# LED.net
KiCad netlist of a schematic drawn in EAGLE
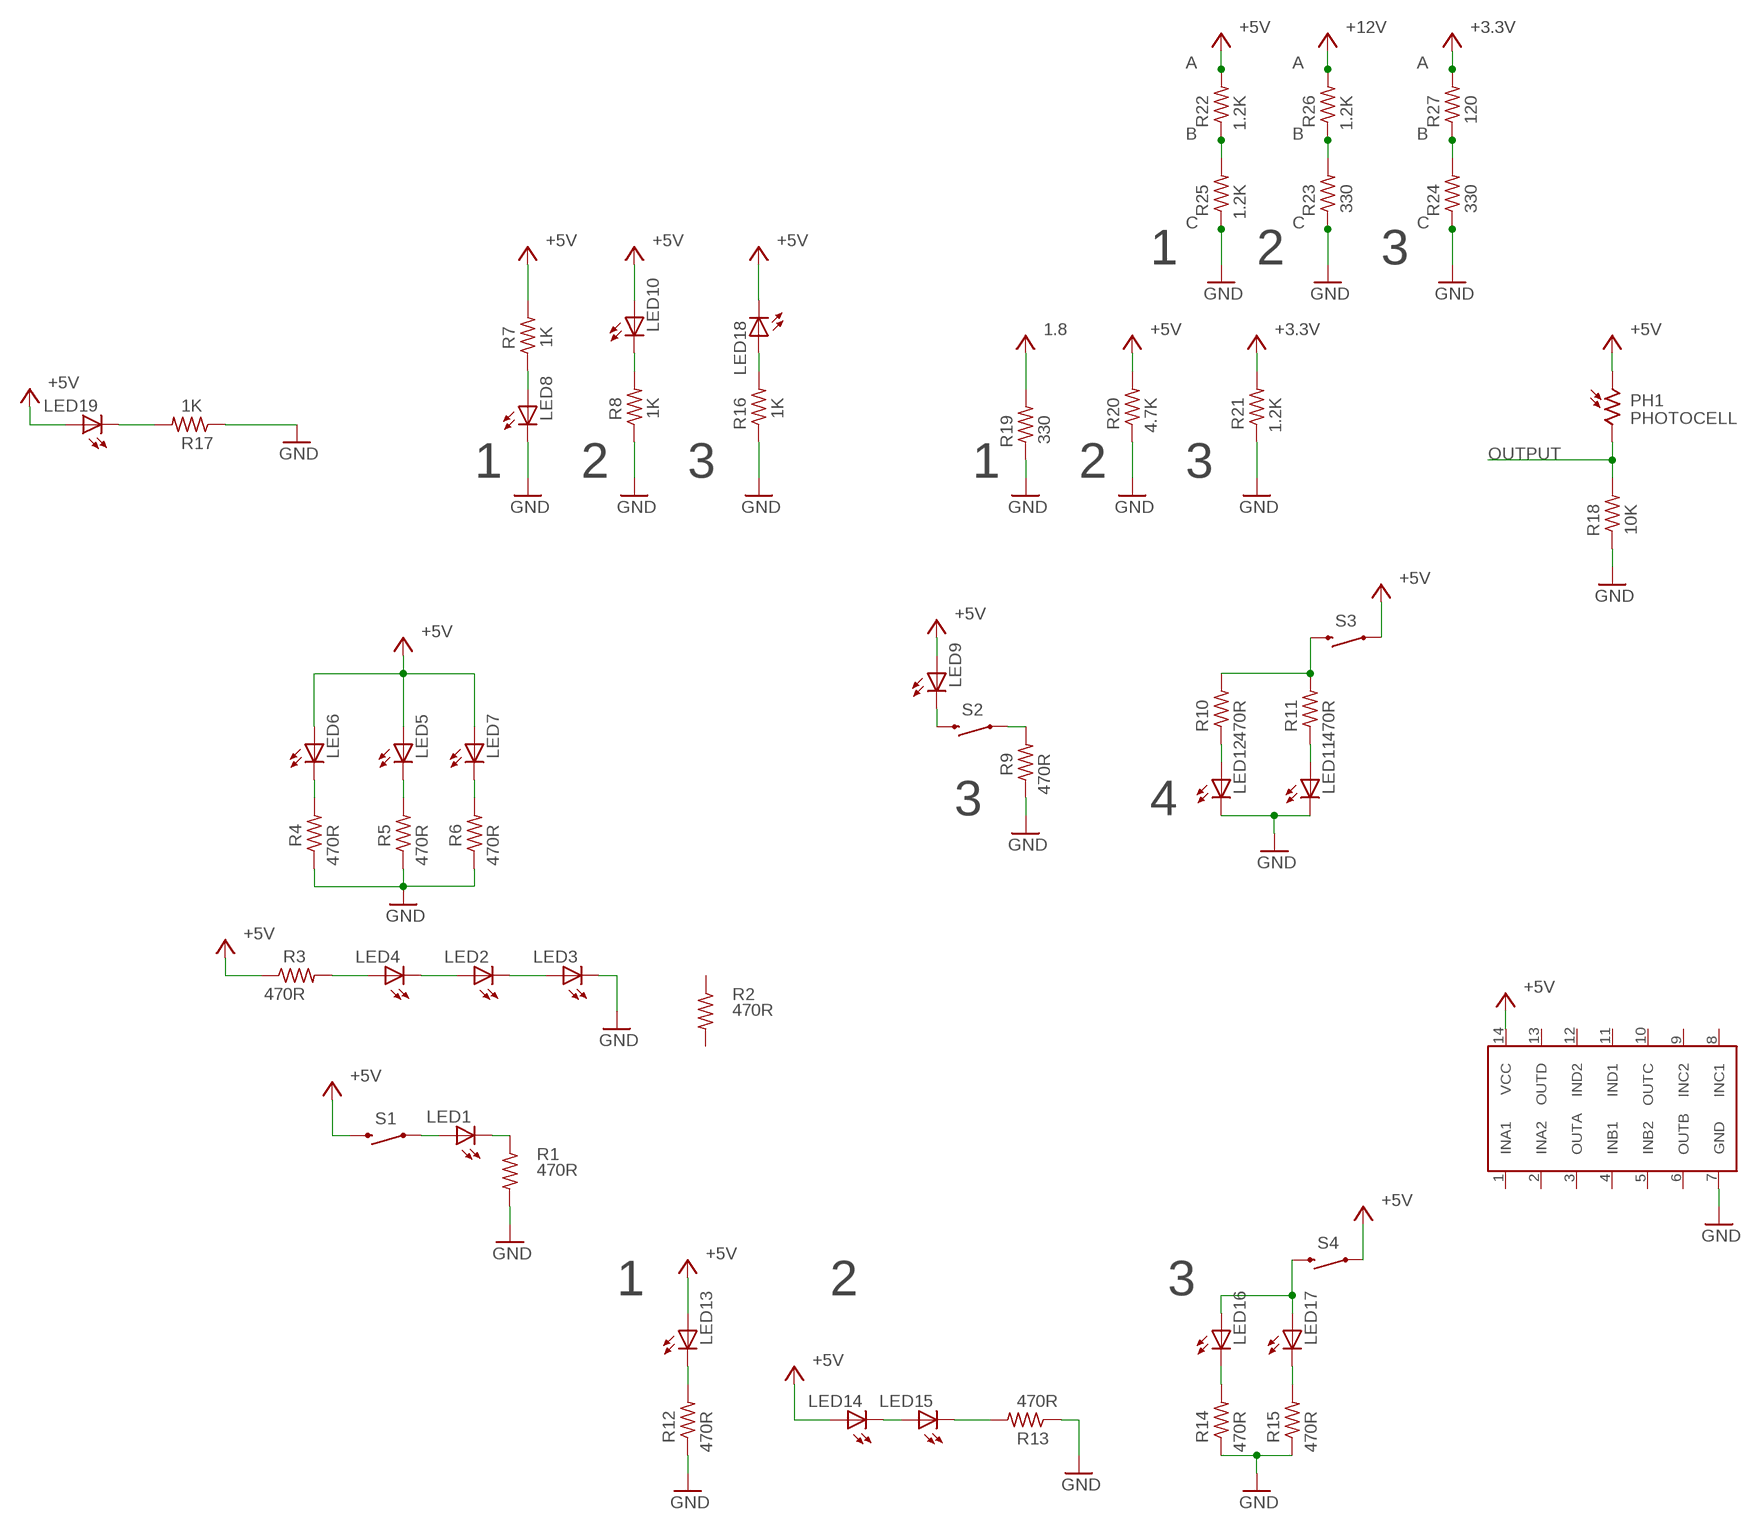
[diagram p0: schematic, sheet 1]

(export (version "E")
  (design (tool "Eeschema 10.0.6"))
  (components
    (comp (ref "LED1")
      (value "LAP4-BOTTOM")
      (footprint "eagle-import:P47F-BOTTOM")
      (libsource (lib "eagle-import") (part "P4-BOTTOMLA"))
    )
    (comp (ref "LED2")
      (value "LAP4-BOTTOM")
      (footprint "eagle-import:P47F-BOTTOM")
      (libsource (lib "eagle-import") (part "P4-BOTTOMLA"))
    )
    (comp (ref "LED3")
      (value "LAP4-BOTTOM")
      (footprint "eagle-import:P47F-BOTTOM")
      (libsource (lib "eagle-import") (part "P4-BOTTOMLA"))
    )
    (comp (ref "LED4")
      (value "LAP4-BOTTOM")
      (footprint "eagle-import:P47F-BOTTOM")
      (libsource (lib "eagle-import") (part "P4-BOTTOMLA"))
    )
    (comp (ref "LED5")
      (value "LAP4-BOTTOM")
      (footprint "eagle-import:P47F-BOTTOM")
      (libsource (lib "eagle-import") (part "P4-BOTTOMLA"))
    )
    (comp (ref "LED6")
      (value "LAP4-BOTTOM")
      (footprint "eagle-import:P47F-BOTTOM")
      (libsource (lib "eagle-import") (part "P4-BOTTOMLA"))
    )
    (comp (ref "LED7")
      (value "LAP4-BOTTOM")
      (footprint "eagle-import:P47F-BOTTOM")
      (libsource (lib "eagle-import") (part "P4-BOTTOMLA"))
    )
    (comp (ref "LED8")
      (value "LAP4-BOTTOM")
      (footprint "eagle-import:P47F-BOTTOM")
      (libsource (lib "eagle-import") (part "P4-BOTTOMLA"))
    )
    (comp (ref "LED9")
      (value "LAP4-BOTTOM")
      (footprint "eagle-import:P47F-BOTTOM")
      (libsource (lib "eagle-import") (part "P4-BOTTOMLA"))
    )
    (comp (ref "LED10")
      (value "LAP4-BOTTOM")
      (footprint "eagle-import:P47F-BOTTOM")
      (libsource (lib "eagle-import") (part "P4-BOTTOMLA"))
    )
    (comp (ref "LED11")
      (value "LAP4-BOTTOM")
      (footprint "eagle-import:P47F-BOTTOM")
      (libsource (lib "eagle-import") (part "P4-BOTTOMLA"))
    )
    (comp (ref "LED12")
      (value "LAP4-BOTTOM")
      (footprint "eagle-import:P47F-BOTTOM")
      (libsource (lib "eagle-import") (part "P4-BOTTOMLA"))
    )
    (comp (ref "LED13")
      (value "LAP4-BOTTOM")
      (footprint "eagle-import:P47F-BOTTOM")
      (libsource (lib "eagle-import") (part "P4-BOTTOMLA"))
    )
    (comp (ref "LED14")
      (value "LAP4-BOTTOM")
      (footprint "eagle-import:P47F-BOTTOM")
      (libsource (lib "eagle-import") (part "P4-BOTTOMLA"))
    )
    (comp (ref "LED15")
      (value "LAP4-BOTTOM")
      (footprint "eagle-import:P47F-BOTTOM")
      (libsource (lib "eagle-import") (part "P4-BOTTOMLA"))
    )
    (comp (ref "LED16")
      (value "LAP4-BOTTOM")
      (footprint "eagle-import:P47F-BOTTOM")
      (libsource (lib "eagle-import") (part "P4-BOTTOMLA"))
    )
    (comp (ref "LED17")
      (value "LAP4-BOTTOM")
      (footprint "eagle-import:P47F-BOTTOM")
      (libsource (lib "eagle-import") (part "P4-BOTTOMLA"))
    )
    (comp (ref "LED18")
      (value "LAP4-BOTTOM")
      (footprint "eagle-import:P47F-BOTTOM")
      (libsource (lib "eagle-import") (part "P4-BOTTOMLA"))
    )
    (comp (ref "LED19")
      (value "LAP4-BOTTOM")
      (footprint "eagle-import:P47F-BOTTOM")
      (libsource (lib "eagle-import") (part "P4-BOTTOMLA"))
    )
    (comp (ref "PH1")
      (value "PHOTOCELL")
      (footprint "eagle-import:D11XX_H")
      (libsource (lib "eagle-import") (part "PHOTOCELLD11"))
    )
    (comp (ref "R1")
      (value "470R")
      (footprint "eagle-import:0207_12")
      (libsource (lib "eagle-import") (part "R-US_0207/12"))
    )
    (comp (ref "R2")
      (value "470R")
      (footprint "eagle-import:0207_12")
      (libsource (lib "eagle-import") (part "R-US_0207/12"))
    )
    (comp (ref "R3")
      (value "470R")
      (footprint "eagle-import:0207_12")
      (libsource (lib "eagle-import") (part "R-US_0207/12"))
    )
    (comp (ref "R4")
      (value "470R")
      (footprint "eagle-import:0207_12")
      (libsource (lib "eagle-import") (part "R-US_0207/12"))
    )
    (comp (ref "R5")
      (value "470R")
      (footprint "eagle-import:0207_12")
      (libsource (lib "eagle-import") (part "R-US_0207/12"))
    )
    (comp (ref "R6")
      (value "470R")
      (footprint "eagle-import:0207_12")
      (libsource (lib "eagle-import") (part "R-US_0207/12"))
    )
    (comp (ref "R7")
      (value "1K")
      (footprint "eagle-import:0207_12")
      (libsource (lib "eagle-import") (part "R-US_0207/12"))
    )
    (comp (ref "R8")
      (value "1K")
      (footprint "eagle-import:0207_12")
      (libsource (lib "eagle-import") (part "R-US_0207/12"))
    )
    (comp (ref "R9")
      (value "470R")
      (footprint "eagle-import:0207_12")
      (libsource (lib "eagle-import") (part "R-US_0207/12"))
    )
    (comp (ref "R10")
      (value "470R")
      (footprint "eagle-import:0207_12")
      (libsource (lib "eagle-import") (part "R-US_0207/12"))
    )
    (comp (ref "R11")
      (value "470R")
      (footprint "eagle-import:0207_12")
      (libsource (lib "eagle-import") (part "R-US_0207/12"))
    )
    (comp (ref "R12")
      (value "470R")
      (footprint "eagle-import:0207_12")
      (libsource (lib "eagle-import") (part "R-US_0207/12"))
    )
    (comp (ref "R13")
      (value "470R")
      (footprint "eagle-import:0207_12")
      (libsource (lib "eagle-import") (part "R-US_0207/12"))
    )
    (comp (ref "R14")
      (value "470R")
      (footprint "eagle-import:0207_12")
      (libsource (lib "eagle-import") (part "R-US_0207/12"))
    )
    (comp (ref "R15")
      (value "470R")
      (footprint "eagle-import:0207_12")
      (libsource (lib "eagle-import") (part "R-US_0207/12"))
    )
    (comp (ref "R16")
      (value "1K")
      (footprint "eagle-import:0207_12")
      (libsource (lib "eagle-import") (part "R-US_0207/12"))
    )
    (comp (ref "R17")
      (value "1K")
      (footprint "eagle-import:0207_12")
      (libsource (lib "eagle-import") (part "R-US_0207/12"))
    )
    (comp (ref "R18")
      (value "10K")
      (footprint "eagle-import:0207_12")
      (libsource (lib "eagle-import") (part "R-US_0207/12"))
    )
    (comp (ref "R19")
      (value "330")
      (footprint "eagle-import:0207_12")
      (libsource (lib "eagle-import") (part "R-US_0207/12"))
    )
    (comp (ref "R20")
      (value "4.7K")
      (footprint "eagle-import:0207_12")
      (libsource (lib "eagle-import") (part "R-US_0207/12"))
    )
    (comp (ref "R21")
      (value "1.2K")
      (footprint "eagle-import:0207_12")
      (libsource (lib "eagle-import") (part "R-US_0207/12"))
    )
    (comp (ref "R22")
      (value "1.2K")
      (footprint "eagle-import:0207_12")
      (libsource (lib "eagle-import") (part "R-US_0207/12"))
    )
    (comp (ref "R23")
      (value "330")
      (footprint "eagle-import:0207_12")
      (libsource (lib "eagle-import") (part "R-US_0207/12"))
    )
    (comp (ref "R24")
      (value "330")
      (footprint "eagle-import:0207_12")
      (libsource (lib "eagle-import") (part "R-US_0207/12"))
    )
    (comp (ref "R25")
      (value "1.2K")
      (footprint "eagle-import:0207_12")
      (libsource (lib "eagle-import") (part "R-US_0207/12"))
    )
    (comp (ref "R26")
      (value "1.2K")
      (footprint "eagle-import:0207_12")
      (libsource (lib "eagle-import") (part "R-US_0207/12"))
    )
    (comp (ref "R27")
      (value "120")
      (footprint "eagle-import:0207_12")
      (libsource (lib "eagle-import") (part "R-US_0207/12"))
    )
    (comp (ref "S1")
      (value "MOMENTARY-SWITCH-SPST-PTH-6.0MM")
      (footprint "eagle-import:TACTILE_SWITCH_PTH_6.0MM")
      (libsource (lib "eagle-import") (part "MOMENTARY-SWITCH-SPST-PTH-6.0MM"))
    )
    (comp (ref "S2")
      (value "MOMENTARY-SWITCH-SPST-PTH-6.0MM")
      (footprint "eagle-import:TACTILE_SWITCH_PTH_6.0MM")
      (libsource (lib "eagle-import") (part "MOMENTARY-SWITCH-SPST-PTH-6.0MM"))
    )
    (comp (ref "S3")
      (value "MOMENTARY-SWITCH-SPST-PTH-6.0MM")
      (footprint "eagle-import:TACTILE_SWITCH_PTH_6.0MM")
      (libsource (lib "eagle-import") (part "MOMENTARY-SWITCH-SPST-PTH-6.0MM"))
    )
    (comp (ref "S4")
      (value "MOMENTARY-SWITCH-SPST-PTH-6.0MM")
      (footprint "eagle-import:TACTILE_SWITCH_PTH_6.0MM")
      (libsource (lib "eagle-import") (part "MOMENTARY-SWITCH-SPST-PTH-6.0MM"))
    )
    (comp (ref "U$1")
      (value "7408")
      (footprint "eagle-import:DIL14")
      (libsource (lib "eagle-import") (part "7408"))
    )
  )
  (nets
    (net (code "1") (name "+12V") (class "Default")
      (node (ref "LED10") (pin "A") (pinfunction "A_A") (pintype "passive"))
      (node (ref "LED13") (pin "A") (pinfunction "A_A") (pintype "passive"))
      (node (ref "LED14") (pin "A") (pinfunction "A_A") (pintype "passive"))
      (node (ref "LED18") (pin "C") (pinfunction "C_C") (pintype "passive"))
      (node (ref "LED19") (pin "A") (pinfunction "A_A") (pintype "passive"))
      (node (ref "LED5") (pin "A") (pinfunction "A_A") (pintype "passive"))
      (node (ref "LED6") (pin "A") (pinfunction "A_A") (pintype "passive"))
      (node (ref "LED7") (pin "A") (pinfunction "A_A") (pintype "passive"))
      (node (ref "LED9") (pin "A") (pinfunction "A_A") (pintype "passive"))
      (node (ref "PH1") (pin "1") (pinfunction "1_1") (pintype "passive"))
      (node (ref "R19") (pin "2") (pinfunction "2_2") (pintype "passive"))
      (node (ref "R20") (pin "2") (pinfunction "2_2") (pintype "passive"))
      (node (ref "R21") (pin "2") (pinfunction "2_2") (pintype "passive"))
      (node (ref "R22") (pin "2") (pinfunction "2_2") (pintype "passive"))
      (node (ref "R26") (pin "2") (pinfunction "2_2") (pintype "passive"))
      (node (ref "R27") (pin "2") (pinfunction "2_2") (pintype "passive"))
      (node (ref "R3") (pin "1") (pinfunction "1_1") (pintype "passive"))
      (node (ref "R7") (pin "2") (pinfunction "2_2") (pintype "passive"))
      (node (ref "S1") (pin "3") (pinfunction "2_3") (pintype "passive"))
      (node (ref "S3") (pin "1") (pinfunction "1_1") (pintype "passive"))
      (node (ref "S4") (pin "1") (pinfunction "1_1") (pintype "passive"))
      (node (ref "U$1") (pin "14") (pinfunction "VCC_14") (pintype "bidirectional"))
    )
    (net (code "2") (name "GND") (class "Default")
      (node (ref "LED11") (pin "C") (pinfunction "C_C") (pintype "passive"))
      (node (ref "LED12") (pin "C") (pinfunction "C_C") (pintype "passive"))
      (node (ref "LED3") (pin "C") (pinfunction "C_C") (pintype "passive"))
      (node (ref "LED8") (pin "C") (pinfunction "C_C") (pintype "passive"))
      (node (ref "R1") (pin "2") (pinfunction "2_2") (pintype "passive"))
      (node (ref "R12") (pin "1") (pinfunction "1_1") (pintype "passive"))
      (node (ref "R13") (pin "1") (pinfunction "1_1") (pintype "passive"))
      (node (ref "R14") (pin "1") (pinfunction "1_1") (pintype "passive"))
      (node (ref "R15") (pin "1") (pinfunction "1_1") (pintype "passive"))
      (node (ref "R16") (pin "1") (pinfunction "1_1") (pintype "passive"))
      (node (ref "R17") (pin "1") (pinfunction "1_1") (pintype "passive"))
      (node (ref "R18") (pin "1") (pinfunction "1_1") (pintype "passive"))
      (node (ref "R19") (pin "1") (pinfunction "1_1") (pintype "passive"))
      (node (ref "R20") (pin "1") (pinfunction "1_1") (pintype "passive"))
      (node (ref "R21") (pin "1") (pinfunction "1_1") (pintype "passive"))
      (node (ref "R23") (pin "1") (pinfunction "1_1") (pintype "passive"))
      (node (ref "R24") (pin "1") (pinfunction "1_1") (pintype "passive"))
      (node (ref "R25") (pin "1") (pinfunction "1_1") (pintype "passive"))
      (node (ref "R4") (pin "1") (pinfunction "1_1") (pintype "passive"))
      (node (ref "R5") (pin "1") (pinfunction "1_1") (pintype "passive"))
      (node (ref "R6") (pin "1") (pinfunction "1_1") (pintype "passive"))
      (node (ref "R8") (pin "1") (pinfunction "1_1") (pintype "passive"))
      (node (ref "R9") (pin "1") (pinfunction "1_1") (pintype "passive"))
      (node (ref "U$1") (pin "7") (pinfunction "GND_7") (pintype "bidirectional"))
    )
    (net (code "3") (name "Net-(LED1-PadA)") (class "Default")
      (node (ref "LED1") (pin "A") (pinfunction "A_A") (pintype "passive"))
      (node (ref "S1") (pin "1") (pinfunction "1_1") (pintype "passive"))
    )
    (net (code "4") (name "Net-(LED1-PadC)") (class "Default")
      (node (ref "LED1") (pin "C") (pinfunction "C_C") (pintype "passive"))
      (node (ref "R1") (pin "1") (pinfunction "1_1") (pintype "passive"))
    )
    (net (code "5") (name "Net-(LED2-PadA)") (class "Default")
      (node (ref "LED2") (pin "A") (pinfunction "A_A") (pintype "passive"))
      (node (ref "LED4") (pin "C") (pinfunction "C_C") (pintype "passive"))
    )
    (net (code "6") (name "Net-(LED2-PadC)") (class "Default")
      (node (ref "LED2") (pin "C") (pinfunction "C_C") (pintype "passive"))
      (node (ref "LED3") (pin "A") (pinfunction "A_A") (pintype "passive"))
    )
    (net (code "7") (name "Net-(LED4-PadA)") (class "Default")
      (node (ref "LED4") (pin "A") (pinfunction "A_A") (pintype "passive"))
      (node (ref "R3") (pin "2") (pinfunction "2_2") (pintype "passive"))
    )
    (net (code "8") (name "Net-(LED5-PadC)") (class "Default")
      (node (ref "LED5") (pin "C") (pinfunction "C_C") (pintype "passive"))
      (node (ref "R5") (pin "2") (pinfunction "2_2") (pintype "passive"))
    )
    (net (code "9") (name "Net-(LED6-PadC)") (class "Default")
      (node (ref "LED6") (pin "C") (pinfunction "C_C") (pintype "passive"))
      (node (ref "R4") (pin "2") (pinfunction "2_2") (pintype "passive"))
    )
    (net (code "10") (name "Net-(LED7-PadC)") (class "Default")
      (node (ref "LED7") (pin "C") (pinfunction "C_C") (pintype "passive"))
      (node (ref "R6") (pin "2") (pinfunction "2_2") (pintype "passive"))
    )
    (net (code "11") (name "Net-(LED8-PadA)") (class "Default")
      (node (ref "LED8") (pin "A") (pinfunction "A_A") (pintype "passive"))
      (node (ref "R7") (pin "1") (pinfunction "1_1") (pintype "passive"))
    )
    (net (code "12") (name "Net-(LED10-PadC)") (class "Default")
      (node (ref "LED10") (pin "C") (pinfunction "C_C") (pintype "passive"))
      (node (ref "R8") (pin "2") (pinfunction "2_2") (pintype "passive"))
    )
    (net (code "13") (name "Net-(LED11-PadA)") (class "Default")
      (node (ref "LED11") (pin "A") (pinfunction "A_A") (pintype "passive"))
      (node (ref "R11") (pin "1") (pinfunction "1_1") (pintype "passive"))
    )
    (net (code "14") (name "Net-(LED12-PadA)") (class "Default")
      (node (ref "LED12") (pin "A") (pinfunction "A_A") (pintype "passive"))
      (node (ref "R10") (pin "1") (pinfunction "1_1") (pintype "passive"))
    )
    (net (code "15") (name "Net-(LED13-PadC)") (class "Default")
      (node (ref "LED13") (pin "C") (pinfunction "C_C") (pintype "passive"))
      (node (ref "R12") (pin "2") (pinfunction "2_2") (pintype "passive"))
    )
    (net (code "16") (name "Net-(LED14-PadC)") (class "Default")
      (node (ref "LED14") (pin "C") (pinfunction "C_C") (pintype "passive"))
      (node (ref "LED15") (pin "A") (pinfunction "A_A") (pintype "passive"))
    )
    (net (code "17") (name "Net-(LED15-PadC)") (class "Default")
      (node (ref "LED15") (pin "C") (pinfunction "C_C") (pintype "passive"))
      (node (ref "R13") (pin "2") (pinfunction "2_2") (pintype "passive"))
    )
    (net (code "18") (name "Net-(LED16-PadC)") (class "Default")
      (node (ref "LED16") (pin "C") (pinfunction "C_C") (pintype "passive"))
      (node (ref "R14") (pin "2") (pinfunction "2_2") (pintype "passive"))
    )
    (net (code "19") (name "Net-(LED17-PadC)") (class "Default")
      (node (ref "LED17") (pin "C") (pinfunction "C_C") (pintype "passive"))
      (node (ref "R15") (pin "2") (pinfunction "2_2") (pintype "passive"))
    )
    (net (code "20") (name "Net-(LED18-PadA)") (class "Default")
      (node (ref "LED18") (pin "A") (pinfunction "A_A") (pintype "passive"))
      (node (ref "R16") (pin "2") (pinfunction "2_2") (pintype "passive"))
    )
    (net (code "21") (name "Net-(LED19-PadC)") (class "Default")
      (node (ref "LED19") (pin "C") (pinfunction "C_C") (pintype "passive"))
      (node (ref "R17") (pin "2") (pinfunction "2_2") (pintype "passive"))
    )
    (net (code "22") (name "Net-(PH1-Pad2)") (class "Default")
      (node (ref "PH1") (pin "2") (pinfunction "2_2") (pintype "passive"))
      (node (ref "R18") (pin "2") (pinfunction "2_2") (pintype "passive"))
    )
    (net (code "23") (name "Net-(R9-Pad2)") (class "Default")
      (node (ref "R9") (pin "2") (pinfunction "2_2") (pintype "passive"))
      (node (ref "S2") (pin "1") (pinfunction "1_1") (pintype "passive"))
    )
    (net (code "24") (name "Net-(R22-Pad1)") (class "Default")
      (node (ref "R22") (pin "1") (pinfunction "1_1") (pintype "passive"))
      (node (ref "R25") (pin "2") (pinfunction "2_2") (pintype "passive"))
    )
    (net (code "25") (name "Net-(R23-Pad2)") (class "Default")
      (node (ref "R23") (pin "2") (pinfunction "2_2") (pintype "passive"))
      (node (ref "R26") (pin "1") (pinfunction "1_1") (pintype "passive"))
    )
    (net (code "26") (name "Net-(R24-Pad2)") (class "Default")
      (node (ref "R24") (pin "2") (pinfunction "2_2") (pintype "passive"))
      (node (ref "R27") (pin "1") (pinfunction "1_1") (pintype "passive"))
    )
    (net (code "27") (name "Net-(S2-2)") (class "Default")
      (node (ref "LED9") (pin "C") (pinfunction "C_C") (pintype "passive"))
      (node (ref "S2") (pin "3") (pinfunction "2_3") (pintype "passive"))
    )
    (net (code "28") (name "Net-(S3-2)") (class "Default")
      (node (ref "R10") (pin "2") (pinfunction "2_2") (pintype "passive"))
      (node (ref "R11") (pin "2") (pinfunction "2_2") (pintype "passive"))
      (node (ref "S3") (pin "3") (pinfunction "2_3") (pintype "passive"))
    )
    (net (code "29") (name "Net-(S4-2)") (class "Default")
      (node (ref "LED16") (pin "A") (pinfunction "A_A") (pintype "passive"))
      (node (ref "LED17") (pin "A") (pinfunction "A_A") (pintype "passive"))
      (node (ref "S4") (pin "3") (pinfunction "2_3") (pintype "passive"))
    )
    (net (code "30") (name "unconnected-(R2-Pad1)") (class "Default")
      (node (ref "R2") (pin "1") (pinfunction "1_1") (pintype "passive"))
    )
    (net (code "31") (name "unconnected-(R2-Pad2)") (class "Default")
      (node (ref "R2") (pin "2") (pinfunction "2_2") (pintype "passive"))
    )
    (net (code "32") (name "unconnected-(U$1-INA1-Pad1)") (class "Default")
      (node (ref "U$1") (pin "1") (pinfunction "INA1_1") (pintype "bidirectional"))
    )
    (net (code "33") (name "unconnected-(U$1-INA2-Pad2)") (class "Default")
      (node (ref "U$1") (pin "2") (pinfunction "INA2_2") (pintype "bidirectional"))
    )
    (net (code "34") (name "unconnected-(U$1-INB1-Pad4)") (class "Default")
      (node (ref "U$1") (pin "4") (pinfunction "INB1_4") (pintype "bidirectional"))
    )
    (net (code "35") (name "unconnected-(U$1-INB2-Pad5)") (class "Default")
      (node (ref "U$1") (pin "5") (pinfunction "INB2_5") (pintype "bidirectional"))
    )
    (net (code "36") (name "unconnected-(U$1-INC1-Pad8)") (class "Default")
      (node (ref "U$1") (pin "8") (pinfunction "INC1_8") (pintype "bidirectional"))
    )
    (net (code "37") (name "unconnected-(U$1-INC2-Pad9)") (class "Default")
      (node (ref "U$1") (pin "9") (pinfunction "INC2_9") (pintype "bidirectional"))
    )
    (net (code "38") (name "unconnected-(U$1-IND1-Pad11)") (class "Default")
      (node (ref "U$1") (pin "11") (pinfunction "IND1_11") (pintype "bidirectional"))
    )
    (net (code "39") (name "unconnected-(U$1-IND2-Pad12)") (class "Default")
      (node (ref "U$1") (pin "12") (pinfunction "IND2_12") (pintype "bidirectional"))
    )
    (net (code "40") (name "unconnected-(U$1-OUTA-Pad3)") (class "Default")
      (node (ref "U$1") (pin "3") (pinfunction "OUTA_3") (pintype "bidirectional"))
    )
    (net (code "41") (name "unconnected-(U$1-OUTB-Pad6)") (class "Default")
      (node (ref "U$1") (pin "6") (pinfunction "OUTB_6") (pintype "bidirectional"))
    )
    (net (code "42") (name "unconnected-(U$1-OUTC-Pad10)") (class "Default")
      (node (ref "U$1") (pin "10") (pinfunction "OUTC_10") (pintype "bidirectional"))
    )
    (net (code "43") (name "unconnected-(U$1-OUTD-Pad13)") (class "Default")
      (node (ref "U$1") (pin "13") (pinfunction "OUTD_13") (pintype "bidirectional"))
    )
  )
)
